# SCH.net
KiCad netlist of a schematic drawn in EasyEDA
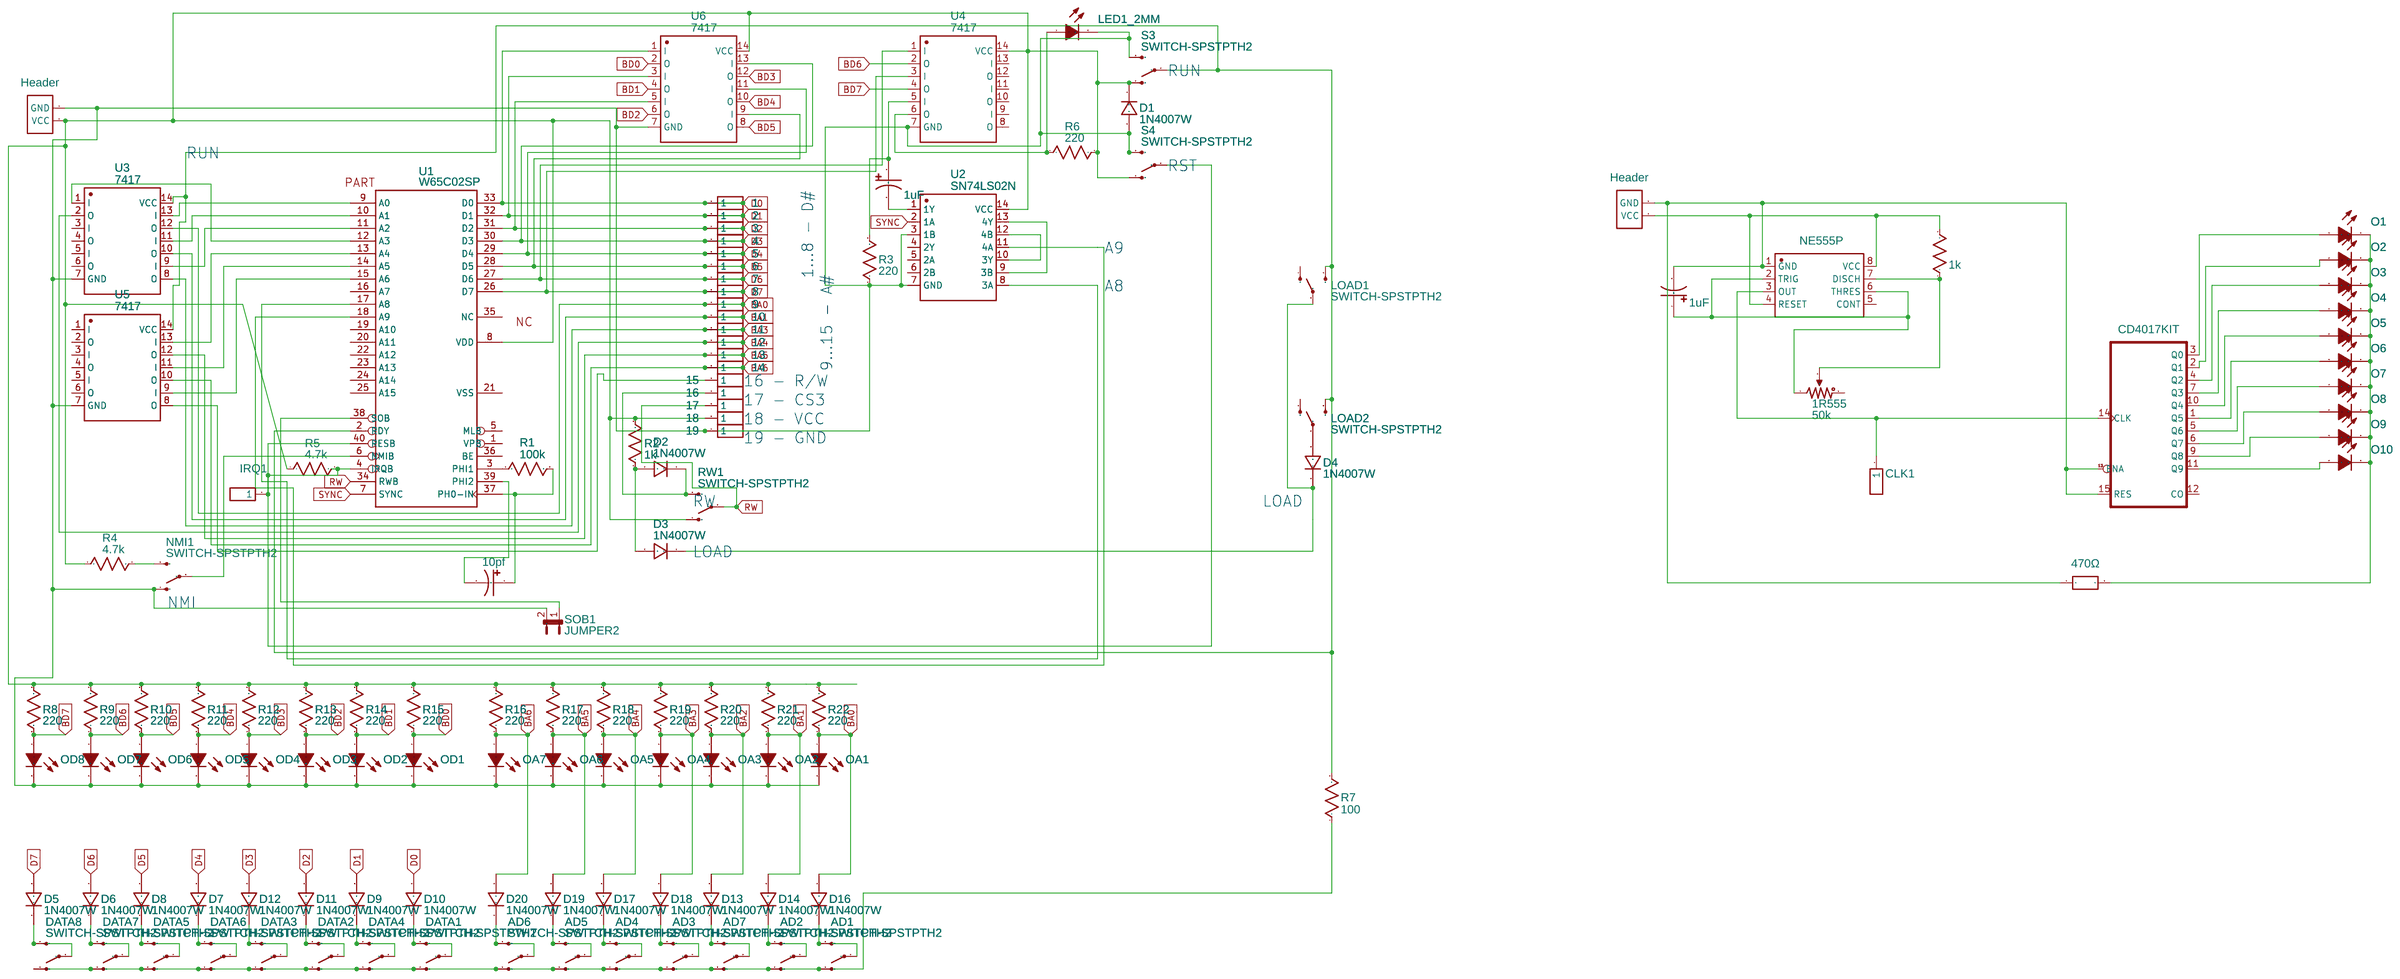
[diagram p0: schematic sheet]

(export (version "E")
  (design (tool "Eeschema 10.0.6"))
  (components
    (comp (ref "1")
      (value "C81276")
      (fields
        (field (name "Manufacturer Part") "2.54-1*1P针")
        (field (name "Manufacturer") "BOOMELE(Boom Precision Elec)")
      )
      (libsource (lib "") (part "Header-Male-2.54_1x1"))
    )
    (comp (ref "1R555")
      (value "50k")
      (fields (field (name "Manufacturer Part") "?"))
      (libsource (lib "") (part "Potentiometer"))
    )
    (comp (ref "2")
      (value "C81276")
      (fields
        (field (name "Manufacturer Part") "2.54-1*1P针")
        (field (name "Manufacturer") "BOOMELE(Boom Precision Elec)")
      )
      (libsource (lib "") (part "Header-Male-2.54_1x1"))
    )
    (comp (ref "2R555")
      (value "1k")
      (fields (field (name "Manufacturer Part") "?"))
      (libsource (lib "") (part "Resistor"))
    )
    (comp (ref "3")
      (value "C81276")
      (fields
        (field (name "Manufacturer Part") "2.54-1*1P针")
        (field (name "Manufacturer") "BOOMELE(Boom Precision Elec)")
      )
      (libsource (lib "") (part "Header-Male-2.54_1x1"))
    )
    (comp (ref "4")
      (value "C81276")
      (fields
        (field (name "Manufacturer Part") "2.54-1*1P针")
        (field (name "Manufacturer") "BOOMELE(Boom Precision Elec)")
      )
      (libsource (lib "") (part "Header-Male-2.54_1x1"))
    )
    (comp (ref "5")
      (value "C81276")
      (fields
        (field (name "Manufacturer Part") "2.54-1*1P针")
        (field (name "Manufacturer") "BOOMELE(Boom Precision Elec)")
      )
      (libsource (lib "") (part "Header-Male-2.54_1x1"))
    )
    (comp (ref "6")
      (value "C81276")
      (fields
        (field (name "Manufacturer Part") "2.54-1*1P针")
        (field (name "Manufacturer") "BOOMELE(Boom Precision Elec)")
      )
      (libsource (lib "") (part "Header-Male-2.54_1x1"))
    )
    (comp (ref "7")
      (value "C81276")
      (fields
        (field (name "Manufacturer Part") "2.54-1*1P针")
        (field (name "Manufacturer") "BOOMELE(Boom Precision Elec)")
      )
      (libsource (lib "") (part "Header-Male-2.54_1x1"))
    )
    (comp (ref "8")
      (value "C81276")
      (fields
        (field (name "Manufacturer Part") "2.54-1*1P针")
        (field (name "Manufacturer") "BOOMELE(Boom Precision Elec)")
      )
      (libsource (lib "") (part "Header-Male-2.54_1x1"))
    )
    (comp (ref "9")
      (value "C81276")
      (fields
        (field (name "Manufacturer Part") "2.54-1*1P针")
        (field (name "Manufacturer") "BOOMELE(Boom Precision Elec)")
      )
      (libsource (lib "") (part "Header-Male-2.54_1x1"))
    )
    (comp (ref "10")
      (value "C81276")
      (fields
        (field (name "Manufacturer Part") "2.54-1*1P针")
        (field (name "Manufacturer") "BOOMELE(Boom Precision Elec)")
      )
      (libsource (lib "") (part "Header-Male-2.54_1x1"))
    )
    (comp (ref "11")
      (value "C81276")
      (fields
        (field (name "Manufacturer Part") "2.54-1*1P针")
        (field (name "Manufacturer") "BOOMELE(Boom Precision Elec)")
      )
      (libsource (lib "") (part "Header-Male-2.54_1x1"))
    )
    (comp (ref "12")
      (value "C81276")
      (fields
        (field (name "Manufacturer Part") "2.54-1*1P针")
        (field (name "Manufacturer") "BOOMELE(Boom Precision Elec)")
      )
      (libsource (lib "") (part "Header-Male-2.54_1x1"))
    )
    (comp (ref "13")
      (value "C81276")
      (fields
        (field (name "Manufacturer Part") "2.54-1*1P针")
        (field (name "Manufacturer") "BOOMELE(Boom Precision Elec)")
      )
      (libsource (lib "") (part "Header-Male-2.54_1x1"))
    )
    (comp (ref "14")
      (value "C81276")
      (fields
        (field (name "Manufacturer Part") "2.54-1*1P针")
        (field (name "Manufacturer") "BOOMELE(Boom Precision Elec)")
      )
      (libsource (lib "") (part "Header-Male-2.54_1x1"))
    )
    (comp (ref "15")
      (value "C81276")
      (fields
        (field (name "Manufacturer Part") "2.54-1*1P针")
        (field (name "Manufacturer") "BOOMELE(Boom Precision Elec)")
      )
      (libsource (lib "") (part "Header-Male-2.54_1x1"))
    )
    (comp (ref "16")
      (value "C81276")
      (fields
        (field (name "Manufacturer Part") "2.54-1*1P针")
        (field (name "Manufacturer") "BOOMELE(Boom Precision Elec)")
      )
      (libsource (lib "") (part "Header-Male-2.54_1x1"))
    )
    (comp (ref "17")
      (value "C81276")
      (fields
        (field (name "Manufacturer Part") "2.54-1*1P针")
        (field (name "Manufacturer") "BOOMELE(Boom Precision Elec)")
      )
      (libsource (lib "") (part "Header-Male-2.54_1x1"))
    )
    (comp (ref "18")
      (value "C81276")
      (fields
        (field (name "Manufacturer Part") "2.54-1*1P针")
        (field (name "Manufacturer") "BOOMELE(Boom Precision Elec)")
      )
      (libsource (lib "") (part "Header-Male-2.54_1x1"))
    )
    (comp (ref "19")
      (value "C81276")
      (fields
        (field (name "Manufacturer Part") "2.54-1*1P针")
        (field (name "Manufacturer") "BOOMELE(Boom Precision Elec)")
      )
      (libsource (lib "") (part "Header-Male-2.54_1x1"))
    )
    (comp (ref "300HEADER") (value "Header") (libsource (lib "") (part "HEADER-FEMALE-2.54_1X2_1")))
    (comp (ref "555")
      (value "NE555P")
      (fields (field (name "Manufacturer") "TI(德州仪器)"))
      (libsource (lib "") (part "NE555P"))
    )
    (comp (ref "555HEADER") (value "Header") (libsource (lib "") (part "HEADER-FEMALE-2.54_1X2")))
    (comp (ref "555U5") (value "CD4017KIT") (libsource (lib "") (part "CD4017KIT")))
    (comp (ref "AD1") (value "SWITCH-SPSTPTH2") (libsource (lib "") (part "SWITCH-SPSTPTH2_1")))
    (comp (ref "AD2") (value "SWITCH-SPSTPTH2") (libsource (lib "") (part "SWITCH-SPSTPTH2_1")))
    (comp (ref "AD3") (value "SWITCH-SPSTPTH2") (libsource (lib "") (part "SWITCH-SPSTPTH2_1")))
    (comp (ref "AD4") (value "SWITCH-SPSTPTH2") (libsource (lib "") (part "SWITCH-SPSTPTH2_1")))
    (comp (ref "AD5") (value "SWITCH-SPSTPTH2") (libsource (lib "") (part "SWITCH-SPSTPTH2_1")))
    (comp (ref "AD6") (value "SWITCH-SPSTPTH2") (libsource (lib "") (part "SWITCH-SPSTPTH2_1")))
    (comp (ref "AD7") (value "SWITCH-SPSTPTH2") (libsource (lib "") (part "SWITCH-SPSTPTH2_1")))
    (comp (ref "C1")
      (value "1uF")
      (fields (field (name "Manufacturer Part") "UVZ1H010MDD") (field (name "Manufacturer") "Nichicon(尼吉康)"))
      (libsource (lib "") (part "UVZ1H010MDD_1"))
    )
    (comp (ref "C2")
      (value "10pf")
      (fields (field (name "Manufacturer Part") "UVZ1H010MDD") (field (name "Manufacturer") "Nichicon(尼吉康)"))
      (libsource (lib "") (part "UVZ1H010MDD_2"))
    )
    (comp (ref "CAP555")
      (value "1uF")
      (fields (field (name "Manufacturer Part") "UVZ1H010MDD") (field (name "Manufacturer") "Nichicon(尼吉康)"))
      (libsource (lib "") (part "UVZ1H010MDD"))
    )
    (comp (ref "CLK1")
      (value "C81276")
      (fields
        (field (name "Manufacturer Part") "2.54-1*1P针")
        (field (name "Manufacturer") "BOOMELE(Boom Precision Elec)")
      )
      (libsource (lib "") (part "Header-Male-2.54_1x1_2"))
    )
    (comp (ref "D1")
      (value "1N4007W")
      (fields (field (name "Manufacturer") "BLUE ROCKET"))
      (libsource (lib "") (part "1N4007W"))
    )
    (comp (ref "D2")
      (value "1N4007W")
      (fields (field (name "Manufacturer") "BLUE ROCKET"))
      (libsource (lib "") (part "1N4007W_1"))
    )
    (comp (ref "D3")
      (value "1N4007W")
      (fields (field (name "Manufacturer") "BLUE ROCKET"))
      (libsource (lib "") (part "1N4007W_1"))
    )
    (comp (ref "D4")
      (value "1N4007W")
      (fields (field (name "Manufacturer") "BLUE ROCKET"))
      (libsource (lib "") (part "1N4007W_2"))
    )
    (comp (ref "D5")
      (value "1N4007W")
      (fields (field (name "Manufacturer") "BLUE ROCKET"))
      (libsource (lib "") (part "1N4007W_2"))
    )
    (comp (ref "D6")
      (value "1N4007W")
      (fields (field (name "Manufacturer") "BLUE ROCKET"))
      (libsource (lib "") (part "1N4007W_2"))
    )
    (comp (ref "D7")
      (value "1N4007W")
      (fields (field (name "Manufacturer") "BLUE ROCKET"))
      (libsource (lib "") (part "1N4007W_2"))
    )
    (comp (ref "D8")
      (value "1N4007W")
      (fields (field (name "Manufacturer") "BLUE ROCKET"))
      (libsource (lib "") (part "1N4007W_2"))
    )
    (comp (ref "D9")
      (value "1N4007W")
      (fields (field (name "Manufacturer") "BLUE ROCKET"))
      (libsource (lib "") (part "1N4007W_2"))
    )
    (comp (ref "D10")
      (value "1N4007W")
      (fields (field (name "Manufacturer") "BLUE ROCKET"))
      (libsource (lib "") (part "1N4007W_2"))
    )
    (comp (ref "D11")
      (value "1N4007W")
      (fields (field (name "Manufacturer") "BLUE ROCKET"))
      (libsource (lib "") (part "1N4007W_2"))
    )
    (comp (ref "D12")
      (value "1N4007W")
      (fields (field (name "Manufacturer") "BLUE ROCKET"))
      (libsource (lib "") (part "1N4007W_2"))
    )
    (comp (ref "D13")
      (value "1N4007W")
      (fields (field (name "Manufacturer") "BLUE ROCKET"))
      (libsource (lib "") (part "1N4007W_2"))
    )
    (comp (ref "D14")
      (value "1N4007W")
      (fields (field (name "Manufacturer") "BLUE ROCKET"))
      (libsource (lib "") (part "1N4007W_2"))
    )
    (comp (ref "D16")
      (value "1N4007W")
      (fields (field (name "Manufacturer") "BLUE ROCKET"))
      (libsource (lib "") (part "1N4007W_2"))
    )
    (comp (ref "D17")
      (value "1N4007W")
      (fields (field (name "Manufacturer") "BLUE ROCKET"))
      (libsource (lib "") (part "1N4007W_2"))
    )
    (comp (ref "D18")
      (value "1N4007W")
      (fields (field (name "Manufacturer") "BLUE ROCKET"))
      (libsource (lib "") (part "1N4007W_2"))
    )
    (comp (ref "D19")
      (value "1N4007W")
      (fields (field (name "Manufacturer") "BLUE ROCKET"))
      (libsource (lib "") (part "1N4007W_2"))
    )
    (comp (ref "D20")
      (value "1N4007W")
      (fields (field (name "Manufacturer") "BLUE ROCKET"))
      (libsource (lib "") (part "1N4007W_2"))
    )
    (comp (ref "DATA1") (value "SWITCH-SPSTPTH2") (libsource (lib "") (part "SWITCH-SPSTPTH2")))
    (comp (ref "DATA2") (value "SWITCH-SPSTPTH2") (libsource (lib "") (part "SWITCH-SPSTPTH2")))
    (comp (ref "DATA3") (value "SWITCH-SPSTPTH2") (libsource (lib "") (part "SWITCH-SPSTPTH2")))
    (comp (ref "DATA4") (value "SWITCH-SPSTPTH2") (libsource (lib "") (part "SWITCH-SPSTPTH2")))
    (comp (ref "DATA5") (value "SWITCH-SPSTPTH2") (libsource (lib "") (part "SWITCH-SPSTPTH2")))
    (comp (ref "DATA6") (value "SWITCH-SPSTPTH2") (libsource (lib "") (part "SWITCH-SPSTPTH2")))
    (comp (ref "DATA7") (value "SWITCH-SPSTPTH2") (libsource (lib "") (part "SWITCH-SPSTPTH2")))
    (comp (ref "DATA8") (value "SWITCH-SPSTPTH2") (libsource (lib "") (part "SWITCH-SPSTPTH2")))
    (comp (ref "IRQ1")
      (value "C81276")
      (fields
        (field (name "Manufacturer Part") "2.54-1*1P针")
        (field (name "Manufacturer") "BOOMELE(Boom Precision Elec)")
      )
      (libsource (lib "") (part "Header-Male-2.54_1x1_1"))
    )
    (comp (ref "LED1_2MM") (value "LED_5MM") (libsource (lib "") (part "LED_5MM_3")))
    (comp (ref "LOAD1") (value "SWITCH-SPSTPTH2") (libsource (lib "") (part "SWITCH-SPSTPTH2_5")))
    (comp (ref "LOAD2") (value "SWITCH-SPSTPTH2") (libsource (lib "") (part "SWITCH-SPSTPTH2_5")))
    (comp (ref "NMI1") (value "SWITCH-SPSTPTH2") (libsource (lib "") (part "SWITCH-SPSTPTH2_3")))
    (comp (ref "O1") (value "LED_5MM") (libsource (lib "") (part "LED_5MM_2")))
    (comp (ref "O2") (value "LED_5MM") (libsource (lib "") (part "LED_5MM_2")))
    (comp (ref "O3") (value "LED_5MM") (libsource (lib "") (part "LED_5MM_2")))
    (comp (ref "O4") (value "LED_5MM") (libsource (lib "") (part "LED_5MM_2")))
    (comp (ref "O5") (value "LED_5MM") (libsource (lib "") (part "LED_5MM_2")))
    (comp (ref "O6") (value "LED_5MM") (libsource (lib "") (part "LED_5MM_2")))
    (comp (ref "O7") (value "LED_5MM") (libsource (lib "") (part "LED_5MM_2")))
    (comp (ref "O8") (value "LED_5MM") (libsource (lib "") (part "LED_5MM_2")))
    (comp (ref "O9") (value "LED_5MM") (libsource (lib "") (part "LED_5MM_2")))
    (comp (ref "O10") (value "LED_5MM") (libsource (lib "") (part "LED_5MM_2")))
    (comp (ref "OA1") (value "LED_5MM") (libsource (lib "") (part "LED_5MM")))
    (comp (ref "OA2") (value "LED_5MM") (libsource (lib "") (part "LED_5MM")))
    (comp (ref "OA3") (value "LED_5MM") (libsource (lib "") (part "LED_5MM")))
    (comp (ref "OA4") (value "LED_5MM") (libsource (lib "") (part "LED_5MM")))
    (comp (ref "OA5") (value "LED_5MM") (libsource (lib "") (part "LED_5MM")))
    (comp (ref "OA6") (value "LED_5MM") (libsource (lib "") (part "LED_5MM")))
    (comp (ref "OA7") (value "LED_5MM") (libsource (lib "") (part "LED_5MM")))
    (comp (ref "OD1") (value "LED_5MM") (libsource (lib "") (part "LED_5MM_1")))
    (comp (ref "OD2") (value "LED_5MM") (libsource (lib "") (part "LED_5MM_1")))
    (comp (ref "OD3") (value "LED_5MM") (libsource (lib "") (part "LED_5MM_1")))
    (comp (ref "OD4") (value "LED_5MM") (libsource (lib "") (part "LED_5MM_1")))
    (comp (ref "OD5") (value "LED_5MM") (libsource (lib "") (part "LED_5MM_1")))
    (comp (ref "OD6") (value "LED_5MM") (libsource (lib "") (part "LED_5MM_1")))
    (comp (ref "OD7") (value "LED_5MM") (libsource (lib "") (part "LED_5MM_1")))
    (comp (ref "OD8") (value "LED_5MM") (libsource (lib "") (part "LED_5MM_1")))
    (comp (ref "R1") (value "100k") (libsource (lib "") (part "R_0603_US_1")))
    (comp (ref "R2") (value "1k") (libsource (lib "") (part "R_0603_US")))
    (comp (ref "R3") (value "220") (libsource (lib "") (part "R_0603_US")))
    (comp (ref "R4") (value "4.7k") (libsource (lib "") (part "R_0603_US_1")))
    (comp (ref "R5") (value "4.7k") (libsource (lib "") (part "R_0603_US_1")))
    (comp (ref "R6") (value "220") (libsource (lib "") (part "R_0603_US_1")))
    (comp (ref "R7") (value "100") (libsource (lib "") (part "R_0603_US")))
    (comp (ref "R8") (value "220") (libsource (lib "") (part "R_0603_US")))
    (comp (ref "R9") (value "220") (libsource (lib "") (part "R_0603_US")))
    (comp (ref "R10") (value "220") (libsource (lib "") (part "R_0603_US")))
    (comp (ref "R11") (value "220") (libsource (lib "") (part "R_0603_US")))
    (comp (ref "R12") (value "220") (libsource (lib "") (part "R_0603_US")))
    (comp (ref "R13") (value "220") (libsource (lib "") (part "R_0603_US")))
    (comp (ref "R14") (value "220") (libsource (lib "") (part "R_0603_US")))
    (comp (ref "R15") (value "220") (libsource (lib "") (part "R_0603_US")))
    (comp (ref "R16") (value "220") (libsource (lib "") (part "R_0603_US")))
    (comp (ref "R17") (value "220") (libsource (lib "") (part "R_0603_US")))
    (comp (ref "R18") (value "220") (libsource (lib "") (part "R_0603_US")))
    (comp (ref "R19") (value "220") (libsource (lib "") (part "R_0603_US")))
    (comp (ref "R20") (value "220") (libsource (lib "") (part "R_0603_US")))
    (comp (ref "R21") (value "220") (libsource (lib "") (part "R_0603_US")))
    (comp (ref "R22") (value "220") (libsource (lib "") (part "R_0603_US")))
    (comp (ref "RW1") (value "SWITCH-SPSTPTH2") (libsource (lib "") (part "SWITCH-SPSTPTH2_4")))
    (comp (ref "S3") (value "SWITCH-SPSTPTH2") (libsource (lib "") (part "SWITCH-SPSTPTH2_2")))
    (comp (ref "S4") (value "SWITCH-SPSTPTH2") (libsource (lib "") (part "SWITCH-SPSTPTH2_2")))
    (comp (ref "SOB1") (value "JUMPER2") (libsource (lib "") (part "JUMPER2")))
    (comp (ref "U1") (value "W65C02SP") (libsource (lib "") (part "W65C02SP")))
    (comp (ref "U2") (value "SN74LS02N") (libsource (lib "") (part "SN74LS02N")))
    (comp (ref "U3") (value "7417") (libsource (lib "") (part "7417")))
    (comp (ref "U4") (value "7417") (libsource (lib "") (part "7417")))
    (comp (ref "U5") (value "7417") (libsource (lib "") (part "7417")))
    (comp (ref "U6") (value "7417") (libsource (lib "") (part "7417")))
    (comp (ref "U555")
      (value "470Ω")
      (fields (field (name "Manufacturer Part") "RSF-50JT-52-470R") (field (name "Manufacturer") "YAGEO(国巨)"))
      (libsource (lib "") (part "RSF-50JT-52-470R"))
    )
  )
  (nets
    (net (code "1") (name "BA0") (class "Default")
      (node (ref "9") (pin "1") (pinfunction "1_1") (pintype "unspecified"))
      (node (ref "D16") (pin "2") (pinfunction "2_2") (pintype "unspecified"))
      (node (ref "OA1") (pin "1") (pinfunction "A_1") (pintype "input"))
      (node (ref "R22") (pin "1") (pinfunction "1_1") (pintype "unspecified"))
      (node (ref "U3") (pin "12") (pinfunction "O_12") (pintype "unspecified"))
    )
    (net (code "2") (name "BA1") (class "Default")
      (node (ref "10") (pin "1") (pinfunction "1_1") (pintype "unspecified"))
      (node (ref "D14") (pin "2") (pinfunction "2_2") (pintype "unspecified"))
      (node (ref "OA2") (pin "1") (pinfunction "A_1") (pintype "input"))
      (node (ref "R21") (pin "1") (pinfunction "1_1") (pintype "unspecified"))
      (node (ref "U3") (pin "10") (pinfunction "O_10") (pintype "unspecified"))
    )
    (net (code "3") (name "BA2") (class "Default")
      (node (ref "D13") (pin "2") (pinfunction "2_2") (pintype "unspecified"))
      (node (ref "OA3") (pin "1") (pinfunction "A_1") (pintype "input"))
      (node (ref "R20") (pin "1") (pinfunction "1_1") (pintype "unspecified"))
    )
    (net (code "4") (name "BA3") (class "Default")
      (node (ref "11") (pin "1") (pinfunction "1_1") (pintype "unspecified"))
      (node (ref "D18") (pin "2") (pinfunction "2_2") (pintype "unspecified"))
      (node (ref "OA4") (pin "1") (pinfunction "A_1") (pintype "input"))
      (node (ref "R19") (pin "1") (pinfunction "1_1") (pintype "unspecified"))
      (node (ref "U3") (pin "8") (pinfunction "O_8") (pintype "unspecified"))
    )
    (net (code "5") (name "BA4") (class "Default")
      (node (ref "12") (pin "1") (pinfunction "1_1") (pintype "unspecified"))
      (node (ref "D17") (pin "2") (pinfunction "2_2") (pintype "unspecified"))
      (node (ref "OA5") (pin "1") (pinfunction "A_1") (pintype "input"))
      (node (ref "R18") (pin "1") (pinfunction "1_1") (pintype "unspecified"))
      (node (ref "U3") (pin "2") (pinfunction "O_2") (pintype "unspecified"))
    )
    (net (code "6") (name "BA5") (class "Default")
      (node (ref "13") (pin "1") (pinfunction "1_1") (pintype "unspecified"))
      (node (ref "D19") (pin "2") (pinfunction "2_2") (pintype "unspecified"))
      (node (ref "OA6") (pin "1") (pinfunction "A_1") (pintype "input"))
      (node (ref "R17") (pin "1") (pinfunction "1_1") (pintype "unspecified"))
      (node (ref "U5") (pin "12") (pinfunction "O_12") (pintype "unspecified"))
    )
    (net (code "7") (name "BA6") (class "Default")
      (node (ref "14") (pin "1") (pinfunction "1_1") (pintype "unspecified"))
      (node (ref "D20") (pin "2") (pinfunction "2_2") (pintype "unspecified"))
      (node (ref "OA7") (pin "1") (pinfunction "A_1") (pintype "input"))
      (node (ref "R16") (pin "1") (pinfunction "1_1") (pintype "unspecified"))
      (node (ref "U5") (pin "10") (pinfunction "O_10") (pintype "unspecified"))
    )
    (net (code "8") (name "BD0") (class "Default")
      (node (ref "OD1") (pin "1") (pinfunction "A_1") (pintype "input"))
      (node (ref "R15") (pin "1") (pinfunction "1_1") (pintype "unspecified"))
      (node (ref "U6") (pin "2") (pinfunction "O_2") (pintype "unspecified"))
    )
    (net (code "9") (name "BD1") (class "Default")
      (node (ref "OD2") (pin "1") (pinfunction "A_1") (pintype "input"))
      (node (ref "R14") (pin "1") (pinfunction "1_1") (pintype "unspecified"))
      (node (ref "U6") (pin "4") (pinfunction "O_4") (pintype "unspecified"))
    )
    (net (code "10") (name "BD2") (class "Default")
      (node (ref "OD3") (pin "1") (pinfunction "A_1") (pintype "input"))
      (node (ref "R13") (pin "1") (pinfunction "1_1") (pintype "unspecified"))
      (node (ref "U6") (pin "6") (pinfunction "O_6") (pintype "unspecified"))
    )
    (net (code "11") (name "BD3") (class "Default")
      (node (ref "OD4") (pin "1") (pinfunction "A_1") (pintype "input"))
      (node (ref "R12") (pin "1") (pinfunction "1_1") (pintype "unspecified"))
      (node (ref "U6") (pin "12") (pinfunction "O_12") (pintype "unspecified"))
    )
    (net (code "12") (name "BD4") (class "Default")
      (node (ref "OD5") (pin "1") (pinfunction "A_1") (pintype "input"))
      (node (ref "R11") (pin "1") (pinfunction "1_1") (pintype "unspecified"))
      (node (ref "U6") (pin "10") (pinfunction "O_10") (pintype "unspecified"))
    )
    (net (code "13") (name "BD5") (class "Default")
      (node (ref "OD6") (pin "1") (pinfunction "A_1") (pintype "input"))
      (node (ref "R10") (pin "1") (pinfunction "1_1") (pintype "unspecified"))
      (node (ref "U6") (pin "8") (pinfunction "O_8") (pintype "unspecified"))
    )
    (net (code "14") (name "BD6") (class "Default")
      (node (ref "OD7") (pin "1") (pinfunction "A_1") (pintype "input"))
      (node (ref "R9") (pin "1") (pinfunction "1_1") (pintype "unspecified"))
      (node (ref "U4") (pin "2") (pinfunction "O_2") (pintype "unspecified"))
    )
    (net (code "15") (name "BD7") (class "Default")
      (node (ref "OD8") (pin "1") (pinfunction "A_1") (pintype "input"))
      (node (ref "R8") (pin "1") (pinfunction "1_1") (pintype "unspecified"))
      (node (ref "U4") (pin "4") (pinfunction "O_4") (pintype "unspecified"))
    )
    (net (code "16") (name "D0") (class "Default")
      (node (ref "1") (pin "1") (pinfunction "1_1") (pintype "unspecified"))
      (node (ref "D10") (pin "2") (pinfunction "2_2") (pintype "unspecified"))
      (node (ref "U1") (pin "33") (pinfunction "D0_33") (pintype "unspecified"))
      (node (ref "U6") (pin "1") (pinfunction "I_1") (pintype "unspecified"))
    )
    (net (code "17") (name "D1") (class "Default")
      (node (ref "2") (pin "1") (pinfunction "1_1") (pintype "unspecified"))
      (node (ref "D9") (pin "2") (pinfunction "2_2") (pintype "unspecified"))
      (node (ref "U1") (pin "32") (pinfunction "D1_32") (pintype "unspecified"))
      (node (ref "U6") (pin "3") (pinfunction "I_3") (pintype "unspecified"))
    )
    (net (code "18") (name "D2") (class "Default")
      (node (ref "3") (pin "1") (pinfunction "1_1") (pintype "unspecified"))
      (node (ref "D11") (pin "2") (pinfunction "2_2") (pintype "unspecified"))
      (node (ref "U1") (pin "31") (pinfunction "D2_31") (pintype "unspecified"))
      (node (ref "U6") (pin "5") (pinfunction "I_5") (pintype "unspecified"))
    )
    (net (code "19") (name "D3") (class "Default")
      (node (ref "4") (pin "1") (pinfunction "1_1") (pintype "unspecified"))
      (node (ref "D12") (pin "2") (pinfunction "2_2") (pintype "unspecified"))
      (node (ref "U1") (pin "30") (pinfunction "D3_30") (pintype "unspecified"))
      (node (ref "U6") (pin "13") (pinfunction "I_13") (pintype "unspecified"))
    )
    (net (code "20") (name "D4") (class "Default")
      (node (ref "5") (pin "1") (pinfunction "1_1") (pintype "unspecified"))
      (node (ref "D7") (pin "2") (pinfunction "2_2") (pintype "unspecified"))
      (node (ref "U1") (pin "29") (pinfunction "D4_29") (pintype "unspecified"))
      (node (ref "U6") (pin "11") (pinfunction "I_11") (pintype "unspecified"))
    )
    (net (code "21") (name "D5") (class "Default")
      (node (ref "6") (pin "1") (pinfunction "1_1") (pintype "unspecified"))
      (node (ref "D8") (pin "2") (pinfunction "2_2") (pintype "unspecified"))
      (node (ref "U1") (pin "28") (pinfunction "D5_28") (pintype "unspecified"))
      (node (ref "U6") (pin "9") (pinfunction "I_9") (pintype "unspecified"))
    )
    (net (code "22") (name "D6") (class "Default")
      (node (ref "7") (pin "1") (pinfunction "1_1") (pintype "unspecified"))
      (node (ref "D6") (pin "2") (pinfunction "2_2") (pintype "unspecified"))
      (node (ref "U1") (pin "27") (pinfunction "D6_27") (pintype "unspecified"))
      (node (ref "U4") (pin "1") (pinfunction "I_1") (pintype "unspecified"))
    )
    (net (code "23") (name "D7") (class "Default")
      (node (ref "8") (pin "1") (pinfunction "1_1") (pintype "unspecified"))
      (node (ref "D5") (pin "2") (pinfunction "2_2") (pintype "unspecified"))
      (node (ref "U1") (pin "26") (pinfunction "D7_26") (pintype "unspecified"))
      (node (ref "U4") (pin "3") (pinfunction "I_3") (pintype "unspecified"))
    )
    (net (code "24") (name "Net-(1R555-3)") (class "Default")
      (node (ref "1R555") (pin "2") (pinfunction "3_2") (pintype "unspecified"))
      (node (ref "2R555") (pin "1") (pinfunction "1_1") (pintype "unspecified"))
      (node (ref "555") (pin "7") (pinfunction "DISCH_7") (pintype "unspecified"))
    )
    (net (code "25") (name "Net-(15-Pad1)") (class "Default")
      (node (ref "15") (pin "1") (pinfunction "1_1") (pintype "unspecified"))
      (node (ref "U5") (pin "8") (pinfunction "O_8") (pintype "unspecified"))
    )
    (net (code "26") (name "Net-(300HEADER-GND)") (class "Default")
      (node (ref "19") (pin "1") (pinfunction "1_1") (pintype "unspecified"))
      (node (ref "300HEADER") (pin "2") (pinfunction "GND_2") (pintype "unspecified"))
      (node (ref "D1") (pin "2") (pinfunction "2_2") (pintype "unspecified"))
      (node (ref "LED1_2MM") (pin "2") (pinfunction "K_2") (pintype "input"))
      (node (ref "NMI1") (pin "1") (pinfunction "O_1") (pintype "unspecified"))
      (node (ref "OA1") (pin "2") (pinfunction "K_2") (pintype "input"))
      (node (ref "OA2") (pin "2") (pinfunction "K_2") (pintype "input"))
      (node (ref "OA3") (pin "2") (pinfunction "K_2") (pintype "input"))
      (node (ref "OA4") (pin "2") (pinfunction "K_2") (pintype "input"))
      (node (ref "OA5") (pin "2") (pinfunction "K_2") (pintype "input"))
      (node (ref "OA6") (pin "2") (pinfunction "K_2") (pintype "input"))
      (node (ref "OA7") (pin "2") (pinfunction "K_2") (pintype "input"))
      (node (ref "OD1") (pin "2") (pinfunction "K_2") (pintype "input"))
      (node (ref "OD2") (pin "2") (pinfunction "K_2") (pintype "input"))
      (node (ref "OD3") (pin "2") (pinfunction "K_2") (pintype "input"))
      (node (ref "OD4") (pin "2") (pinfunction "K_2") (pintype "input"))
      (node (ref "OD5") (pin "2") (pinfunction "K_2") (pintype "input"))
      (node (ref "OD6") (pin "2") (pinfunction "K_2") (pintype "input"))
      (node (ref "OD7") (pin "2") (pinfunction "K_2") (pintype "input"))
      (node (ref "OD8") (pin "2") (pinfunction "K_2") (pintype "input"))
      (node (ref "R3") (pin "1") (pinfunction "1_1") (pintype "unspecified"))
      (node (ref "S3") (pin "3") (pinfunction "S_3") (pintype "unspecified"))
      (node (ref "S4") (pin "3") (pinfunction "S_3") (pintype "unspecified"))
      (node (ref "SOB1") (pin "2") (pinfunction "2_2") (pintype "unspecified"))
      (node (ref "U2") (pin "3") (pinfunction "1B_3") (pintype "unspecified"))
      (node (ref "U2") (pin "7") (pinfunction "GND_7") (pintype "unspecified"))
      (node (ref "U3") (pin "7") (pinfunction "GND_7") (pintype "unspecified"))
      (node (ref "U4") (pin "7") (pinfunction "GND_7") (pintype "unspecified"))
      (node (ref "U5") (pin "7") (pinfunction "GND_7") (pintype "unspecified"))
      (node (ref "U6") (pin "7") (pinfunction "GND_7") (pintype "unspecified"))
    )
    (net (code "27") (name "Net-(300HEADER-VCC)") (class "Default")
      (node (ref "18") (pin "1") (pinfunction "1_1") (pintype "unspecified"))
      (node (ref "300HEADER") (pin "1") (pinfunction "VCC_1") (pintype "unspecified"))
      (node (ref "D1") (pin "1") (pinfunction "1_1") (pintype "unspecified"))
      (node (ref "R10") (pin "2") (pinfunction "2_2") (pintype "unspecified"))
      (node (ref "R11") (pin "2") (pinfunction "2_2") (pintype "unspecified"))
      (node (ref "R12") (pin "2") (pinfunction "2_2") (pintype "unspecified"))
      (node (ref "R13") (pin "2") (pinfunction "2_2") (pintype "unspecified"))
      (node (ref "R14") (pin "2") (pinfunction "2_2") (pintype "unspecified"))
      (node (ref "R15") (pin "2") (pinfunction "2_2") (pintype "unspecified"))
      (node (ref "R16") (pin "2") (pinfunction "2_2") (pintype "unspecified"))
      (node (ref "R17") (pin "2") (pinfunction "2_2") (pintype "unspecified"))
      (node (ref "R18") (pin "2") (pinfunction "2_2") (pintype "unspecified"))
      (node (ref "R19") (pin "2") (pinfunction "2_2") (pintype "unspecified"))
      (node (ref "R2") (pin "2") (pinfunction "2_2") (pintype "unspecified"))
      (node (ref "R20") (pin "2") (pinfunction "2_2") (pintype "unspecified"))
      (node (ref "R21") (pin "2") (pinfunction "2_2") (pintype "unspecified"))
      (node (ref "R22") (pin "2") (pinfunction "2_2") (pintype "unspecified"))
      (node (ref "R4") (pin "1") (pinfunction "1_1") (pintype "unspecified"))
      (node (ref "R5") (pin "1") (pinfunction "1_1") (pintype "unspecified"))
      (node (ref "R6") (pin "2") (pinfunction "2_2") (pintype "unspecified"))
      (node (ref "R8") (pin "2") (pinfunction "2_2") (pintype "unspecified"))
      (node (ref "R9") (pin "2") (pinfunction "2_2") (pintype "unspecified"))
      (node (ref "RW1") (pin "1") (pinfunction "O_1") (pintype "unspecified"))
      (node (ref "S3") (pin "1") (pinfunction "O_1") (pintype "unspecified"))
      (node (ref "S4") (pin "1") (pinfunction "O_1") (pintype "unspecified"))
      (node (ref "U1") (pin "8") (pinfunction "VDD_8") (pintype "passive"))
      (node (ref "U2") (pin "14") (pinfunction "VCC_14") (pintype "unspecified"))
      (node (ref "U4") (pin "14") (pinfunction "VCC_14") (pintype "unspecified"))
      (node (ref "U6") (pin "14") (pinfunction "VCC_14") (pintype "unspecified"))
    )
    (net (code "28") (name "Net-(555-GND)") (class "Default")
      (node (ref "555") (pin "1") (pinfunction "GND_1") (pintype "unspecified"))
      (node (ref "555HEADER") (pin "2") (pinfunction "GND_2") (pintype "unspecified"))
      (node (ref "555U5") (pin "13") (pinfunction "ENA_13") (pintype "input"))
      (node (ref "555U5") (pin "15") (pinfunction "RES_15") (pintype "input"))
      (node (ref "CAP555") (pin "2") (pinfunction "2_2") (pintype "unspecified"))
      (node (ref "U555") (pin "1") (pinfunction "1_1") (pintype "unspecified"))
    )
    (net (code "29") (name "Net-(555-OUT)") (class "Default")
      (node (ref "555") (pin "3") (pinfunction "OUT_3") (pintype "unspecified"))
      (node (ref "555U5") (pin "14") (pinfunction "CLK_14") (pintype "input"))
      (node (ref "CLK1") (pin "1") (pinfunction "1_1") (pintype "unspecified"))
    )
    (net (code "30") (name "Net-(555-RESET)") (class "Default")
      (node (ref "2R555") (pin "2") (pinfunction "2_2") (pintype "unspecified"))
      (node (ref "555") (pin "4") (pinfunction "RESET_4") (pintype "unspecified"))
      (node (ref "555") (pin "8") (pinfunction "VCC_8") (pintype "unspecified"))
      (node (ref "555HEADER") (pin "1") (pinfunction "VCC_1") (pintype "unspecified"))
    )
    (net (code "31") (name "Net-(555-THRES)") (class "Default")
      (node (ref "1R555") (pin "1") (pinfunction "1_1") (pintype "unspecified"))
      (node (ref "555") (pin "2") (pinfunction "TRIG_2") (pintype "unspecified"))
      (node (ref "555") (pin "6") (pinfunction "THRES_6") (pintype "unspecified"))
      (node (ref "CAP555") (pin "1") (pinfunction "1_1") (pintype "unspecified"))
    )
    (net (code "32") (name "Net-(555U5-Q0)") (class "Default")
      (node (ref "555U5") (pin "3") (pinfunction "Q0_3") (pintype "output"))
      (node (ref "O1") (pin "1") (pinfunction "A_1") (pintype "input"))
    )
    (net (code "33") (name "Net-(555U5-Q1)") (class "Default")
      (node (ref "555U5") (pin "2") (pinfunction "Q1_2") (pintype "output"))
      (node (ref "O2") (pin "1") (pinfunction "A_1") (pintype "input"))
    )
    (net (code "34") (name "Net-(555U5-Q2)") (class "Default")
      (node (ref "555U5") (pin "4") (pinfunction "Q2_4") (pintype "output"))
      (node (ref "O3") (pin "1") (pinfunction "A_1") (pintype "input"))
    )
    (net (code "35") (name "Net-(555U5-Q3)") (class "Default")
      (node (ref "555U5") (pin "7") (pinfunction "Q3_7") (pintype "output"))
      (node (ref "O4") (pin "1") (pinfunction "A_1") (pintype "input"))
    )
    (net (code "36") (name "Net-(555U5-Q4)") (class "Default")
      (node (ref "555U5") (pin "10") (pinfunction "Q4_10") (pintype "output"))
      (node (ref "O5") (pin "1") (pinfunction "A_1") (pintype "input"))
    )
    (net (code "37") (name "Net-(555U5-Q5)") (class "Default")
      (node (ref "555U5") (pin "1") (pinfunction "Q5_1") (pintype "output"))
      (node (ref "O6") (pin "1") (pinfunction "A_1") (pintype "input"))
    )
    (net (code "38") (name "Net-(555U5-Q6)") (class "Default")
      (node (ref "555U5") (pin "5") (pinfunction "Q6_5") (pintype "output"))
      (node (ref "O7") (pin "1") (pinfunction "A_1") (pintype "input"))
    )
    (net (code "39") (name "Net-(555U5-Q7)") (class "Default")
      (node (ref "555U5") (pin "6") (pinfunction "Q7_6") (pintype "output"))
      (node (ref "O8") (pin "1") (pinfunction "A_1") (pintype "input"))
    )
    (net (code "40") (name "Net-(555U5-Q8)") (class "Default")
      (node (ref "555U5") (pin "9") (pinfunction "Q8_9") (pintype "output"))
      (node (ref "O9") (pin "1") (pinfunction "A_1") (pintype "input"))
    )
    (net (code "41") (name "Net-(555U5-Q9)") (class "Default")
      (node (ref "555U5") (pin "11") (pinfunction "Q9_11") (pintype "output"))
      (node (ref "O10") (pin "1") (pinfunction "A_1") (pintype "input"))
    )
    (net (code "42") (name "Net-(AD1-O)") (class "Default")
      (node (ref "AD1") (pin "1") (pinfunction "O_1") (pintype "unspecified"))
      (node (ref "AD2") (pin "1") (pinfunction "O_1") (pintype "unspecified"))
      (node (ref "AD3") (pin "1") (pinfunction "O_1") (pintype "unspecified"))
      (node (ref "AD4") (pin "1") (pinfunction "O_1") (pintype "unspecified"))
      (node (ref "AD5") (pin "1") (pinfunction "O_1") (pintype "unspecified"))
      (node (ref "AD6") (pin "1") (pinfunction "O_1") (pintype "unspecified"))
      (node (ref "AD7") (pin "1") (pinfunction "O_1") (pintype "unspecified"))
      (node (ref "DATA1") (pin "1") (pinfunction "O_1") (pintype "unspecified"))
      (node (ref "DATA2") (pin "1") (pinfunction "O_1") (pintype "unspecified"))
      (node (ref "DATA3") (pin "1") (pinfunction "O_1") (pintype "unspecified"))
      (node (ref "DATA4") (pin "1") (pinfunction "O_1") (pintype "unspecified"))
      (node (ref "DATA5") (pin "1") (pinfunction "O_1") (pintype "unspecified"))
      (node (ref "DATA6") (pin "1") (pinfunction "O_1") (pintype "unspecified"))
      (node (ref "DATA7") (pin "1") (pinfunction "O_1") (pintype "unspecified"))
      (node (ref "DATA8") (pin "1") (pinfunction "O_1") (pintype "unspecified"))
      (node (ref "R7") (pin "1") (pinfunction "1_1") (pintype "unspecified"))
    )
    (net (code "43") (name "Net-(AD1-P)") (class "Default")
      (node (ref "AD1") (pin "2") (pinfunction "P_2") (pintype "unspecified"))
      (node (ref "AD1") (pin "3") (pinfunction "S_3") (pintype "unspecified"))
      (node (ref "D16") (pin "1") (pinfunction "1_1") (pintype "unspecified"))
    )
    (net (code "44") (name "Net-(AD2-P)") (class "Default")
      (node (ref "AD2") (pin "2") (pinfunction "P_2") (pintype "unspecified"))
      (node (ref "AD2") (pin "3") (pinfunction "S_3") (pintype "unspecified"))
      (node (ref "D14") (pin "1") (pinfunction "1_1") (pintype "unspecified"))
    )
    (net (code "45") (name "Net-(AD3-P)") (class "Default")
      (node (ref "AD3") (pin "2") (pinfunction "P_2") (pintype "unspecified"))
      (node (ref "AD3") (pin "3") (pinfunction "S_3") (pintype "unspecified"))
      (node (ref "D18") (pin "1") (pinfunction "1_1") (pintype "unspecified"))
    )
    (net (code "46") (name "Net-(AD4-P)") (class "Default")
      (node (ref "AD4") (pin "2") (pinfunction "P_2") (pintype "unspecified"))
      (node (ref "AD4") (pin "3") (pinfunction "S_3") (pintype "unspecified"))
      (node (ref "D17") (pin "1") (pinfunction "1_1") (pintype "unspecified"))
    )
    (net (code "47") (name "Net-(AD5-P)") (class "Default")
      (node (ref "AD5") (pin "2") (pinfunction "P_2") (pintype "unspecified"))
      (node (ref "AD5") (pin "3") (pinfunction "S_3") (pintype "unspecified"))
      (node (ref "D19") (pin "1") (pinfunction "1_1") (pintype "unspecified"))
    )
    (net (code "48") (name "Net-(AD6-P)") (class "Default")
      (node (ref "AD6") (pin "2") (pinfunction "P_2") (pintype "unspecified"))
      (node (ref "AD6") (pin "3") (pinfunction "S_3") (pintype "unspecified"))
      (node (ref "D20") (pin "1") (pinfunction "1_1") (pintype "unspecified"))
    )
    (net (code "49") (name "Net-(AD7-P)") (class "Default")
      (node (ref "AD7") (pin "2") (pinfunction "P_2") (pintype "unspecified"))
      (node (ref "AD7") (pin "3") (pinfunction "S_3") (pintype "unspecified"))
      (node (ref "D13") (pin "1") (pinfunction "1_1") (pintype "unspecified"))
    )
    (net (code "50") (name "Net-(C1-Pad1)") (class "Default")
      (node (ref "C1") (pin "1") (pinfunction "1_1") (pintype "unspecified"))
      (node (ref "R3") (pin "2") (pinfunction "2_2") (pintype "unspecified"))
      (node (ref "U4") (pin "5") (pinfunction "I_5") (pintype "unspecified"))
    )
    (net (code "51") (name "Net-(D2-Pad2)") (class "Default")
      (node (ref "D2") (pin "2") (pinfunction "2_2") (pintype "unspecified"))
      (node (ref "D3") (pin "2") (pinfunction "2_2") (pintype "unspecified"))
      (node (ref "R2") (pin "1") (pinfunction "1_1") (pintype "unspecified"))
    )
    (net (code "52") (name "Net-(DATA1-P)") (class "Default")
      (node (ref "D10") (pin "1") (pinfunction "1_1") (pintype "unspecified"))
      (node (ref "DATA1") (pin "2") (pinfunction "P_2") (pintype "unspecified"))
      (node (ref "DATA1") (pin "3") (pinfunction "S_3") (pintype "unspecified"))
    )
    (net (code "53") (name "Net-(DATA2-P)") (class "Default")
      (node (ref "D11") (pin "1") (pinfunction "1_1") (pintype "unspecified"))
      (node (ref "DATA2") (pin "2") (pinfunction "P_2") (pintype "unspecified"))
      (node (ref "DATA2") (pin "3") (pinfunction "S_3") (pintype "unspecified"))
    )
    (net (code "54") (name "Net-(DATA3-P)") (class "Default")
      (node (ref "D12") (pin "1") (pinfunction "1_1") (pintype "unspecified"))
      (node (ref "DATA3") (pin "2") (pinfunction "P_2") (pintype "unspecified"))
      (node (ref "DATA3") (pin "3") (pinfunction "S_3") (pintype "unspecified"))
    )
    (net (code "55") (name "Net-(DATA4-P)") (class "Default")
      (node (ref "D9") (pin "1") (pinfunction "1_1") (pintype "unspecified"))
      (node (ref "DATA4") (pin "2") (pinfunction "P_2") (pintype "unspecified"))
      (node (ref "DATA4") (pin "3") (pinfunction "S_3") (pintype "unspecified"))
    )
    (net (code "56") (name "Net-(DATA5-P)") (class "Default")
      (node (ref "D8") (pin "1") (pinfunction "1_1") (pintype "unspecified"))
      (node (ref "DATA5") (pin "2") (pinfunction "P_2") (pintype "unspecified"))
      (node (ref "DATA5") (pin "3") (pinfunction "S_3") (pintype "unspecified"))
    )
    (net (code "57") (name "Net-(DATA6-P)") (class "Default")
      (node (ref "D7") (pin "1") (pinfunction "1_1") (pintype "unspecified"))
      (node (ref "DATA6") (pin "2") (pinfunction "P_2") (pintype "unspecified"))
      (node (ref "DATA6") (pin "3") (pinfunction "S_3") (pintype "unspecified"))
    )
    (net (code "58") (name "Net-(DATA7-P)") (class "Default")
      (node (ref "D6") (pin "1") (pinfunction "1_1") (pintype "unspecified"))
      (node (ref "DATA7") (pin "2") (pinfunction "P_2") (pintype "unspecified"))
      (node (ref "DATA7") (pin "3") (pinfunction "S_3") (pintype "unspecified"))
    )
    (net (code "59") (name "Net-(DATA8-P)") (class "Default")
      (node (ref "D5") (pin "1") (pinfunction "1_1") (pintype "unspecified"))
      (node (ref "DATA8") (pin "2") (pinfunction "P_2") (pintype "unspecified"))
      (node (ref "DATA8") (pin "3") (pinfunction "S_3") (pintype "unspecified"))
    )
    (net (code "60") (name "Net-(LED1_2MM-A)") (class "Default")
      (node (ref "LED1_2MM") (pin "1") (pinfunction "A_1") (pintype "input"))
      (node (ref "R6") (pin "1") (pinfunction "1_1") (pintype "unspecified"))
      (node (ref "U4") (pin "6") (pinfunction "O_6") (pintype "unspecified"))
    )
    (net (code "61") (name "Net-(LOAD1-P)") (class "Default")
      (node (ref "D3") (pin "1") (pinfunction "1_1") (pintype "unspecified"))
      (node (ref "D4") (pin "1") (pinfunction "1_1") (pintype "unspecified"))
      (node (ref "LOAD1") (pin "2") (pinfunction "P_2") (pintype "unspecified"))
    )
    (net (code "62") (name "Net-(LOAD1-S)") (class "Default")
      (node (ref "LOAD1") (pin "3") (pinfunction "S_3") (pintype "unspecified"))
      (node (ref "LOAD2") (pin "3") (pinfunction "S_3") (pintype "unspecified"))
      (node (ref "R7") (pin "2") (pinfunction "2_2") (pintype "unspecified"))
      (node (ref "S3") (pin "2") (pinfunction "P_2") (pintype "unspecified"))
      (node (ref "U1") (pin "2") (pinfunction "RDY_2") (pintype "unspecified"))
      (node (ref "U3") (pin "14") (pinfunction "VCC_14") (pintype "unspecified"))
      (node (ref "U5") (pin "14") (pinfunction "VCC_14") (pintype "unspecified"))
    )
    (net (code "63") (name "Net-(LOAD2-P)") (class "Default")
      (node (ref "D4") (pin "2") (pinfunction "2_2") (pintype "unspecified"))
      (node (ref "LOAD2") (pin "2") (pinfunction "P_2") (pintype "unspecified"))
    )
    (net (code "64") (name "Net-(NMI1-P)") (class "Default")
      (node (ref "NMI1") (pin "2") (pinfunction "P_2") (pintype "unspecified"))
      (node (ref "U1") (pin "6") (pinfunction "NMIB_6") (pintype "input"))
    )
    (net (code "65") (name "Net-(NMI1-S)") (class "Default")
      (node (ref "NMI1") (pin "3") (pinfunction "S_3") (pintype "unspecified"))
      (node (ref "R4") (pin "2") (pinfunction "2_2") (pintype "unspecified"))
    )
    (net (code "66") (name "Net-(O1-K)") (class "Default")
      (node (ref "O1") (pin "2") (pinfunction "K_2") (pintype "input"))
      (node (ref "O10") (pin "2") (pinfunction "K_2") (pintype "input"))
      (node (ref "O2") (pin "2") (pinfunction "K_2") (pintype "input"))
      (node (ref "O3") (pin "2") (pinfunction "K_2") (pintype "input"))
      (node (ref "O4") (pin "2") (pinfunction "K_2") (pintype "input"))
      (node (ref "O5") (pin "2") (pinfunction "K_2") (pintype "input"))
      (node (ref "O6") (pin "2") (pinfunction "K_2") (pintype "input"))
      (node (ref "O7") (pin "2") (pinfunction "K_2") (pintype "input"))
      (node (ref "O8") (pin "2") (pinfunction "K_2") (pintype "input"))
      (node (ref "O9") (pin "2") (pinfunction "K_2") (pintype "input"))
      (node (ref "U555") (pin "2") (pinfunction "2_2") (pintype "unspecified"))
    )
    (net (code "67") (name "Net-(RW1-S)") (class "Default")
      (node (ref "16") (pin "1") (pinfunction "1_1") (pintype "unspecified"))
      (node (ref "D2") (pin "1") (pinfunction "1_1") (pintype "unspecified"))
      (node (ref "RW1") (pin "3") (pinfunction "S_3") (pintype "unspecified"))
    )
    (net (code "68") (name "Net-(S4-P)") (class "Default")
      (node (ref "IRQ1") (pin "1") (pinfunction "1_1") (pintype "unspecified"))
      (node (ref "R5") (pin "2") (pinfunction "2_2") (pintype "unspecified"))
      (node (ref "S4") (pin "2") (pinfunction "P_2") (pintype "unspecified"))
      (node (ref "U1") (pin "4") (pinfunction "IRQB_4") (pintype "input"))
      (node (ref "U1") (pin "40") (pinfunction "RESB_40") (pintype "input"))
    )
    (net (code "69") (name "Net-(U1-A0)") (class "Default")
      (node (ref "U1") (pin "9") (pinfunction "A0_9") (pintype "unspecified"))
      (node (ref "U3") (pin "13") (pinfunction "I_13") (pintype "unspecified"))
    )
    (net (code "70") (name "Net-(U1-A1)") (class "Default")
      (node (ref "U1") (pin "10") (pinfunction "A1_10") (pintype "unspecified"))
      (node (ref "U3") (pin "11") (pinfunction "I_11") (pintype "unspecified"))
    )
    (net (code "71") (name "Net-(U1-A2)") (class "Default")
      (node (ref "U1") (pin "11") (pinfunction "A2_11") (pintype "unspecified"))
      (node (ref "U3") (pin "9") (pinfunction "I_9") (pintype "unspecified"))
    )
    (net (code "72") (name "Net-(U1-A3)") (class "Default")
      (node (ref "U1") (pin "12") (pinfunction "A3_12") (pintype "unspecified"))
      (node (ref "U3") (pin "1") (pinfunction "I_1") (pintype "unspecified"))
    )
    (net (code "73") (name "Net-(U1-A4)") (class "Default")
      (node (ref "U1") (pin "13") (pinfunction "A4_13") (pintype "unspecified"))
      (node (ref "U5") (pin "13") (pinfunction "I_13") (pintype "unspecified"))
    )
    (net (code "74") (name "Net-(U1-A5)") (class "Default")
      (node (ref "U1") (pin "14") (pinfunction "A5_14") (pintype "unspecified"))
      (node (ref "U5") (pin "11") (pinfunction "I_11") (pintype "unspecified"))
    )
    (net (code "75") (name "Net-(U1-A6)") (class "Default")
      (node (ref "U1") (pin "15") (pinfunction "A6_15") (pintype "unspecified"))
      (node (ref "U5") (pin "9") (pinfunction "I_9") (pintype "unspecified"))
    )
    (net (code "76") (name "Net-(U1-A8)") (class "Default")
      (node (ref "U1") (pin "17") (pinfunction "A8_17") (pintype "unspecified"))
      (node (ref "U2") (pin "8") (pinfunction "3A_8") (pintype "unspecified"))
    )
    (net (code "77") (name "Net-(U1-A9)") (class "Default")
      (node (ref "U1") (pin "18") (pinfunction "A9_18") (pintype "unspecified"))
      (node (ref "U2") (pin "11") (pinfunction "4A_11") (pintype "unspecified"))
    )
    (net (code "78") (name "Net-(U1-PH0-IN)") (class "Default")
      (node (ref "C2") (pin "1") (pinfunction "1_1") (pintype "unspecified"))
      (node (ref "R1") (pin "2") (pinfunction "2_2") (pintype "unspecified"))
      (node (ref "U1") (pin "37") (pinfunction "PH0-IN_37") (pintype "input"))
    )
    (net (code "79") (name "Net-(U1-PHI1)") (class "Default")
      (node (ref "R1") (pin "1") (pinfunction "1_1") (pintype "unspecified"))
      (node (ref "U1") (pin "3") (pinfunction "PHI1_3") (pintype "output"))
    )
    (net (code "80") (name "Net-(U1-PHI2)") (class "Default")
      (node (ref "C2") (pin "2") (pinfunction "2_2") (pintype "unspecified"))
      (node (ref "U1") (pin "39") (pinfunction "PHI2_39") (pintype "output"))
    )
    (net (code "81") (name "Net-(U1-SOB)") (class "Default")
      (node (ref "SOB1") (pin "1") (pinfunction "1_1") (pintype "unspecified"))
      (node (ref "U1") (pin "38") (pinfunction "SOB_38") (pintype "input"))
    )
    (net (code "82") (name "Net-(U2-1Y)") (class "Default")
      (node (ref "C1") (pin "2") (pinfunction "2_2") (pintype "unspecified"))
      (node (ref "U2") (pin "1") (pinfunction "1Y_1") (pintype "unspecified"))
    )
    (net (code "83") (name "Net-(U2-3B)") (class "Default")
      (node (ref "U2") (pin "13") (pinfunction "4Y_13") (pintype "unspecified"))
      (node (ref "U2") (pin "9") (pinfunction "3B_9") (pintype "unspecified"))
    )
    (net (code "84") (name "Net-(U2-3Y)") (class "Default")
      (node (ref "U2") (pin "10") (pinfunction "3Y_10") (pintype "unspecified"))
      (node (ref "U2") (pin "12") (pinfunction "4B_12") (pintype "unspecified"))
    )
    (net (code "85") (name "RW") (class "Default")
      (node (ref "17") (pin "1") (pinfunction "1_1") (pintype "unspecified"))
      (node (ref "RW1") (pin "2") (pinfunction "P_2") (pintype "unspecified"))
      (node (ref "U1") (pin "34") (pinfunction "RWB_34") (pintype "output"))
    )
    (net (code "86") (name "SYNC") (class "Default")
      (node (ref "U1") (pin "7") (pinfunction "SYNC_7") (pintype "output"))
      (node (ref "U2") (pin "2") (pinfunction "1A_2") (pintype "unspecified"))
    )
    (net (code "87") (name "unconnected-(1R555-2-Pad3)") (class "Default")
      (node (ref "1R555") (pin "3") (pinfunction "2_3") (pintype "unspecified"))
    )
    (net (code "88") (name "unconnected-(555-CONT-Pad5)") (class "Default")
      (node (ref "555") (pin "5") (pinfunction "CONT_5") (pintype "unspecified"))
    )
    (net (code "89") (name "unconnected-(555U5-CO-Pad12)") (class "Default")
      (node (ref "555U5") (pin "12") (pinfunction "CO_12") (pintype "output"))
    )
    (net (code "90") (name "unconnected-(LOAD1-O-Pad1)") (class "Default")
      (node (ref "LOAD1") (pin "1") (pinfunction "O_1") (pintype "unspecified"))
    )
    (net (code "91") (name "unconnected-(LOAD2-O-Pad1)") (class "Default")
      (node (ref "LOAD2") (pin "1") (pinfunction "O_1") (pintype "unspecified"))
    )
    (net (code "92") (name "unconnected-(U1-A7-Pad16)") (class "Default")
      (node (ref "U1") (pin "16") (pinfunction "A7_16") (pintype "unspecified"))
    )
    (net (code "93") (name "unconnected-(U1-A10-Pad19)") (class "Default")
      (node (ref "U1") (pin "19") (pinfunction "A10_19") (pintype "unspecified"))
    )
    (net (code "94") (name "unconnected-(U1-A11-Pad20)") (class "Default")
      (node (ref "U1") (pin "20") (pinfunction "A11_20") (pintype "unspecified"))
    )
    (net (code "95") (name "unconnected-(U1-A12-Pad22)") (class "Default")
      (node (ref "U1") (pin "22") (pinfunction "A12_22") (pintype "unspecified"))
    )
    (net (code "96") (name "unconnected-(U1-A13-Pad23)") (class "Default")
      (node (ref "U1") (pin "23") (pinfunction "A13_23") (pintype "unspecified"))
    )
    (net (code "97") (name "unconnected-(U1-A14-Pad24)") (class "Default")
      (node (ref "U1") (pin "24") (pinfunction "A14_24") (pintype "unspecified"))
    )
    (net (code "98") (name "unconnected-(U1-A15-Pad25)") (class "Default")
      (node (ref "U1") (pin "25") (pinfunction "A15_25") (pintype "unspecified"))
    )
    (net (code "99") (name "unconnected-(U1-BE-Pad36)") (class "Default")
      (node (ref "U1") (pin "36") (pinfunction "BE_36") (pintype "input"))
    )
    (net (code "100") (name "unconnected-(U1-MLB-Pad5)") (class "Default")
      (node (ref "U1") (pin "5") (pinfunction "MLB_5") (pintype "output"))
    )
    (net (code "101") (name "unconnected-(U1-NC-Pad35)") (class "Default")
      (node (ref "U1") (pin "35") (pinfunction "NC_35") (pintype "unspecified"))
    )
    (net (code "102") (name "unconnected-(U1-VPB-Pad1)") (class "Default")
      (node (ref "U1") (pin "1") (pinfunction "VPB_1") (pintype "output"))
    )
    (net (code "103") (name "unconnected-(U1-VSS-Pad21)") (class "Default")
      (node (ref "U1") (pin "21") (pinfunction "VSS_21") (pintype "unspecified"))
    )
    (net (code "104") (name "unconnected-(U2-2A-Pad5)") (class "Default")
      (node (ref "U2") (pin "5") (pinfunction "2A_5") (pintype "unspecified"))
    )
    (net (code "105") (name "unconnected-(U2-2B-Pad6)") (class "Default")
      (node (ref "U2") (pin "6") (pinfunction "2B_6") (pintype "unspecified"))
    )
    (net (code "106") (name "unconnected-(U2-2Y-Pad4)") (class "Default")
      (node (ref "U2") (pin "4") (pinfunction "2Y_4") (pintype "unspecified"))
    )
    (net (code "107") (name "unconnected-(U3-I-Pad3)") (class "Default")
      (node (ref "U3") (pin "3") (pinfunction "I_3") (pintype "unspecified"))
    )
    (net (code "108") (name "unconnected-(U3-I-Pad5)") (class "Default")
      (node (ref "U3") (pin "5") (pinfunction "I_5") (pintype "unspecified"))
    )
    (net (code "109") (name "unconnected-(U3-O-Pad4)") (class "Default")
      (node (ref "U3") (pin "4") (pinfunction "O_4") (pintype "unspecified"))
    )
    (net (code "110") (name "unconnected-(U3-O-Pad6)") (class "Default")
      (node (ref "U3") (pin "6") (pinfunction "O_6") (pintype "unspecified"))
    )
    (net (code "111") (name "unconnected-(U4-I-Pad9)") (class "Default")
      (node (ref "U4") (pin "9") (pinfunction "I_9") (pintype "unspecified"))
    )
    (net (code "112") (name "unconnected-(U4-I-Pad11)") (class "Default")
      (node (ref "U4") (pin "11") (pinfunction "I_11") (pintype "unspecified"))
    )
    (net (code "113") (name "unconnected-(U4-I-Pad13)") (class "Default")
      (node (ref "U4") (pin "13") (pinfunction "I_13") (pintype "unspecified"))
    )
    (net (code "114") (name "unconnected-(U4-O-Pad8)") (class "Default")
      (node (ref "U4") (pin "8") (pinfunction "O_8") (pintype "unspecified"))
    )
    (net (code "115") (name "unconnected-(U4-O-Pad10)") (class "Default")
      (node (ref "U4") (pin "10") (pinfunction "O_10") (pintype "unspecified"))
    )
    (net (code "116") (name "unconnected-(U4-O-Pad12)") (class "Default")
      (node (ref "U4") (pin "12") (pinfunction "O_12") (pintype "unspecified"))
    )
    (net (code "117") (name "unconnected-(U5-I-Pad1)") (class "Default")
      (node (ref "U5") (pin "1") (pinfunction "I_1") (pintype "unspecified"))
    )
    (net (code "118") (name "unconnected-(U5-I-Pad3)") (class "Default")
      (node (ref "U5") (pin "3") (pinfunction "I_3") (pintype "unspecified"))
    )
    (net (code "119") (name "unconnected-(U5-I-Pad5)") (class "Default")
      (node (ref "U5") (pin "5") (pinfunction "I_5") (pintype "unspecified"))
    )
    (net (code "120") (name "unconnected-(U5-O-Pad2)") (class "Default")
      (node (ref "U5") (pin "2") (pinfunction "O_2") (pintype "unspecified"))
    )
    (net (code "121") (name "unconnected-(U5-O-Pad4)") (class "Default")
      (node (ref "U5") (pin "4") (pinfunction "O_4") (pintype "unspecified"))
    )
    (net (code "122") (name "unconnected-(U5-O-Pad6)") (class "Default")
      (node (ref "U5") (pin "6") (pinfunction "O_6") (pintype "unspecified"))
    )
  )
)
